# rs232.net
KiCad netlist of a schematic drawn in EAGLE
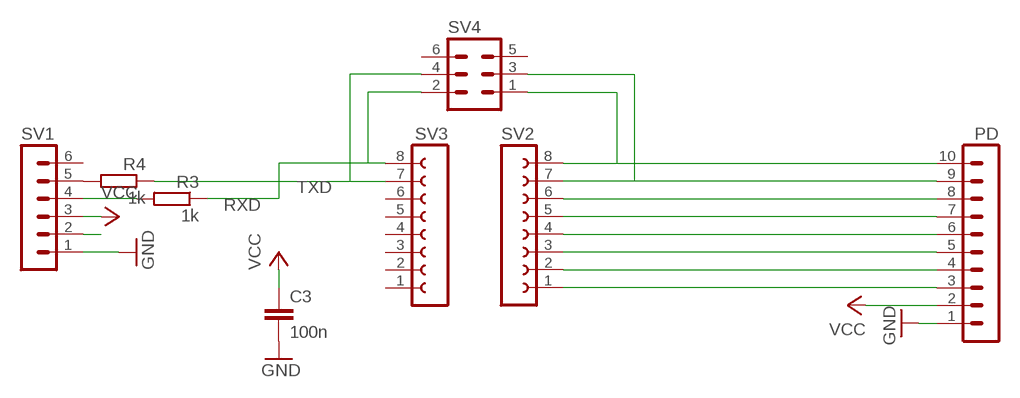
[diagram p0: schematic, sheet 1]

(export (version "E")
  (design (tool "Eeschema 10.0.6"))
  (components
    (comp (ref "C3")
      (value "100n")
      (footprint "eagle-import:C025-024X044")
      (libsource (lib "eagle-import") (part "C-EU025-024X044"))
    )
    (comp (ref "PD")
      (value "MA10-1W")
      (footprint "eagle-import:MA10-1W")
      (libsource (lib "eagle-import") (part "MA10-1W"))
    )
    (comp (ref "R3")
      (value "1k")
      (footprint "eagle-import:0207_12")
      (libsource (lib "eagle-import") (part "R-EU_0207/12"))
    )
    (comp (ref "R4")
      (value "1k")
      (footprint "eagle-import:0207_12")
      (libsource (lib "eagle-import") (part "R-EU_0207/12"))
    )
    (comp (ref "SV1")
      (value "MA06-1")
      (footprint "eagle-import:MA06-1")
      (libsource (lib "eagle-import") (part "MA06-1"))
    )
    (comp (ref "SV2")
      (value "FE08-1")
      (footprint "eagle-import:FE08")
      (libsource (lib "eagle-import") (part "FE08-1"))
    )
    (comp (ref "SV3")
      (value "FE08-1")
      (footprint "eagle-import:FE08")
      (libsource (lib "eagle-import") (part "FE08-1"))
    )
    (comp (ref "SV4")
      (value "MA03-2")
      (footprint "eagle-import:MA03-2")
      (libsource (lib "eagle-import") (part "MA03-2"))
    )
  )
  (nets
    (net (code "1") (name "/RXD") (class "Default")
      (node (ref "R3") (pin "1") (pinfunction "1_1") (pintype "passive"))
      (node (ref "SV3") (pin "8") (pinfunction "8_8") (pintype "passive"))
      (node (ref "SV4") (pin "2") (pinfunction "2_2") (pintype "passive"))
    )
    (net (code "2") (name "/TXD") (class "Default")
      (node (ref "R4") (pin "1") (pinfunction "1_1") (pintype "passive"))
      (node (ref "SV3") (pin "7") (pinfunction "7_7") (pintype "passive"))
      (node (ref "SV4") (pin "4") (pinfunction "4_4") (pintype "passive"))
    )
    (net (code "3") (name "GND") (class "Default")
      (node (ref "C3") (pin "2") (pinfunction "2_2") (pintype "passive"))
      (node (ref "PD") (pin "1") (pinfunction "1_1") (pintype "passive"))
      (node (ref "SV1") (pin "1") (pinfunction "1_1") (pintype "passive"))
    )
    (net (code "4") (name "Net-(PD-Pad3)") (class "Default")
      (node (ref "PD") (pin "3") (pinfunction "3_3") (pintype "passive"))
      (node (ref "SV2") (pin "1") (pinfunction "1_1") (pintype "passive"))
    )
    (net (code "5") (name "Net-(PD-Pad4)") (class "Default")
      (node (ref "PD") (pin "4") (pinfunction "4_4") (pintype "passive"))
      (node (ref "SV2") (pin "2") (pinfunction "2_2") (pintype "passive"))
    )
    (net (code "6") (name "Net-(PD-Pad5)") (class "Default")
      (node (ref "PD") (pin "5") (pinfunction "5_5") (pintype "passive"))
      (node (ref "SV2") (pin "3") (pinfunction "3_3") (pintype "passive"))
    )
    (net (code "7") (name "Net-(PD-Pad6)") (class "Default")
      (node (ref "PD") (pin "6") (pinfunction "6_6") (pintype "passive"))
      (node (ref "SV2") (pin "4") (pinfunction "4_4") (pintype "passive"))
    )
    (net (code "8") (name "Net-(PD-Pad7)") (class "Default")
      (node (ref "PD") (pin "7") (pinfunction "7_7") (pintype "passive"))
      (node (ref "SV2") (pin "5") (pinfunction "5_5") (pintype "passive"))
    )
    (net (code "9") (name "Net-(PD-Pad8)") (class "Default")
      (node (ref "PD") (pin "8") (pinfunction "8_8") (pintype "passive"))
      (node (ref "SV2") (pin "6") (pinfunction "6_6") (pintype "passive"))
    )
    (net (code "10") (name "Net-(PD-Pad9)") (class "Default")
      (node (ref "PD") (pin "9") (pinfunction "9_9") (pintype "passive"))
      (node (ref "SV2") (pin "7") (pinfunction "7_7") (pintype "passive"))
      (node (ref "SV4") (pin "3") (pinfunction "3_3") (pintype "passive"))
    )
    (net (code "11") (name "Net-(PD-Pad10)") (class "Default")
      (node (ref "PD") (pin "10") (pinfunction "10_10") (pintype "passive"))
      (node (ref "SV2") (pin "8") (pinfunction "8_8") (pintype "passive"))
      (node (ref "SV4") (pin "1") (pinfunction "1_1") (pintype "passive"))
    )
    (net (code "12") (name "Net-(R3-Pad2)") (class "Default")
      (node (ref "R3") (pin "2") (pinfunction "2_2") (pintype "passive"))
      (node (ref "SV1") (pin "4") (pinfunction "4_4") (pintype "passive"))
    )
    (net (code "13") (name "Net-(R4-Pad2)") (class "Default")
      (node (ref "R4") (pin "2") (pinfunction "2_2") (pintype "passive"))
      (node (ref "SV1") (pin "5") (pinfunction "5_5") (pintype "passive"))
    )
    (net (code "14") (name "VCC") (class "Default")
      (node (ref "C3") (pin "1") (pinfunction "1_1") (pintype "passive"))
      (node (ref "PD") (pin "2") (pinfunction "2_2") (pintype "passive"))
      (node (ref "SV1") (pin "3") (pinfunction "3_3") (pintype "passive"))
    )
    (net (code "15") (name "unconnected-(SV1-Pad2)") (class "Default")
      (node (ref "SV1") (pin "2") (pinfunction "2_2") (pintype "passive"))
    )
    (net (code "16") (name "unconnected-(SV1-Pad6)") (class "Default")
      (node (ref "SV1") (pin "6") (pinfunction "6_6") (pintype "passive"))
    )
    (net (code "17") (name "unconnected-(SV3-Pad1)") (class "Default")
      (node (ref "SV3") (pin "1") (pinfunction "1_1") (pintype "passive"))
    )
    (net (code "18") (name "unconnected-(SV3-Pad2)") (class "Default")
      (node (ref "SV3") (pin "2") (pinfunction "2_2") (pintype "passive"))
    )
    (net (code "19") (name "unconnected-(SV3-Pad3)") (class "Default")
      (node (ref "SV3") (pin "3") (pinfunction "3_3") (pintype "passive"))
    )
    (net (code "20") (name "unconnected-(SV3-Pad4)") (class "Default")
      (node (ref "SV3") (pin "4") (pinfunction "4_4") (pintype "passive"))
    )
    (net (code "21") (name "unconnected-(SV3-Pad5)") (class "Default")
      (node (ref "SV3") (pin "5") (pinfunction "5_5") (pintype "passive"))
    )
    (net (code "22") (name "unconnected-(SV3-Pad6)") (class "Default")
      (node (ref "SV3") (pin "6") (pinfunction "6_6") (pintype "passive"))
    )
    (net (code "23") (name "unconnected-(SV4-Pad5)") (class "Default")
      (node (ref "SV4") (pin "5") (pinfunction "5_5") (pintype "passive"))
    )
    (net (code "24") (name "unconnected-(SV4-Pad6)") (class "Default")
      (node (ref "SV4") (pin "6") (pinfunction "6_6") (pintype "passive"))
    )
  )
)
